# Janus.net
KiCad netlist of a schematic drawn in EAGLE
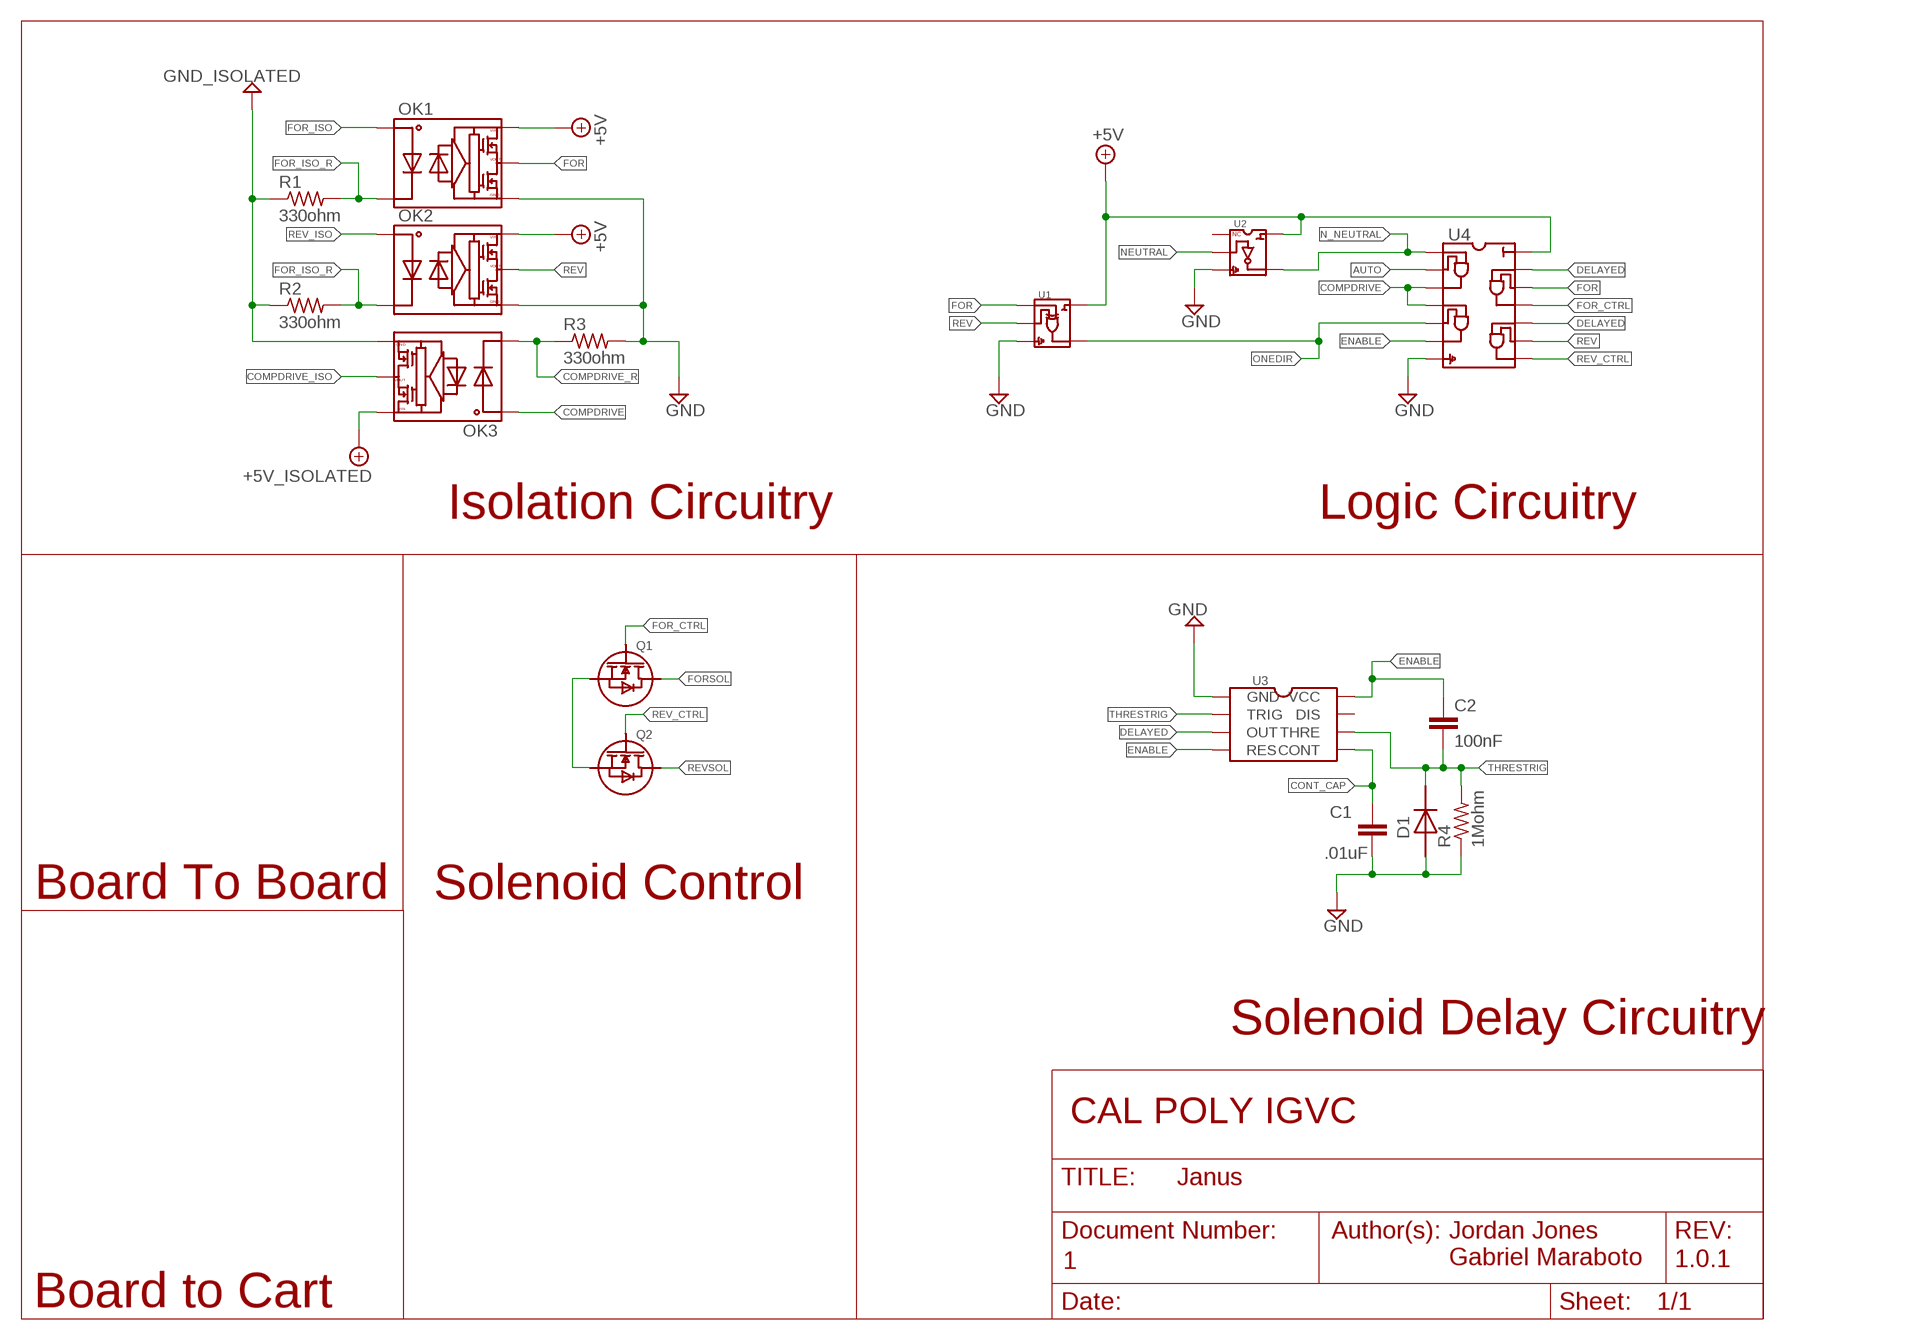
[diagram p0: schematic, sheet 1]

(export (version "E")
  (design (tool "Eeschema 10.0.6"))
  (components
    (comp (ref "C1")
      (value ".01uF")
      (footprint "eagle-import:C0603")
      (libsource (lib "eagle-import") (part "C-EUC0603"))
    )
    (comp (ref "C2")
      (value "100nF")
      (footprint "eagle-import:C0603")
      (libsource (lib "eagle-import") (part "C-EUC0603"))
    )
    (comp (ref "D1")
      (value "1N4148X-TP")
      (footprint "eagle-import:SOD523_SC79")
      (libsource (lib "eagle-import") (part "1N4148X-TP"))
    )
    (comp (ref "OK1")
      (value "TLP152")
      (footprint "eagle-import:6-SOIC-5")
      (libsource (lib "eagle-import") (part "TLP152"))
    )
    (comp (ref "OK2")
      (value "TLP152")
      (footprint "eagle-import:6-SOIC-5")
      (libsource (lib "eagle-import") (part "TLP152"))
    )
    (comp (ref "OK3")
      (value "TLP152")
      (footprint "eagle-import:6-SOIC-5")
      (libsource (lib "eagle-import") (part "TLP152"))
    )
    (comp (ref "Q1")
      (value "DMN6140L-7")
      (footprint "eagle-import:SOT23")
      (libsource (lib "eagle-import") (part "DMN6140L-7"))
    )
    (comp (ref "Q2")
      (value "DMN6140L-7")
      (footprint "eagle-import:SOT23")
      (libsource (lib "eagle-import") (part "DMN6140L-7"))
    )
    (comp (ref "R1")
      (value "330ohm")
      (footprint "eagle-import:R0603")
      (libsource (lib "eagle-import") (part "R-US_R0603"))
    )
    (comp (ref "R2")
      (value "330ohm")
      (footprint "eagle-import:R0603")
      (libsource (lib "eagle-import") (part "R-US_R0603"))
    )
    (comp (ref "R3")
      (value "330ohm")
      (footprint "eagle-import:R0603")
      (libsource (lib "eagle-import") (part "R-US_R0603"))
    )
    (comp (ref "R4")
      (value "1Mohm")
      (footprint "eagle-import:R0603")
      (libsource (lib "eagle-import") (part "R-US_R0603"))
    )
    (comp (ref "U1")
      (value "74LVC1G86W5-7")
      (footprint "eagle-import:SOT-25")
      (libsource (lib "eagle-import") (part "74LVC1G86W5-7"))
    )
    (comp (ref "U2")
      (value "74HCT1G14GW,125")
      (footprint "eagle-import:SOT-353")
      (libsource (lib "eagle-import") (part "74HCT1G14GW,125"))
    )
    (comp (ref "U3")
      (value "NE555S-13DICT-ND")
      (footprint "eagle-import:SO-8")
      (libsource (lib "eagle-import") (part "NE555S-13DICT-ND"))
    )
    (comp (ref "U4")
      (value "SN74LV08APWR")
      (footprint "eagle-import:TSSOP-14")
      (libsource (lib "eagle-import") (part "SN74LV08APWR"))
    )
  )
  (nets
    (net (code "1") (name "+5V") (class "Default")
      (node (ref "OK1") (pin "P$6") (pinfunction "P$6_P$6") (pintype "bidirectional"))
      (node (ref "OK2") (pin "P$6") (pinfunction "P$6_P$6") (pintype "bidirectional"))
      (node (ref "OK3") (pin "P$6") (pinfunction "P$6_P$6") (pintype "bidirectional"))
      (node (ref "U1") (pin "P$5") (pinfunction "P$5_P$5") (pintype "bidirectional"))
      (node (ref "U2") (pin "P$5") (pinfunction "P$5_P$5") (pintype "bidirectional"))
      (node (ref "U4") (pin "P$14") (pinfunction "P$14_P$14") (pintype "bidirectional"))
    )
    (net (code "2") (name "AUTO") (class "Default")
      (node (ref "U4") (pin "P$2") (pinfunction "P$2_P$2") (pintype "bidirectional"))
    )
    (net (code "3") (name "COMPDRIVE") (class "Default")
      (node (ref "OK3") (pin "P$1") (pinfunction "P$1_P$1") (pintype "bidirectional"))
      (node (ref "U4") (pin "P$3") (pinfunction "P$3_P$3") (pintype "bidirectional"))
      (node (ref "U4") (pin "P$4") (pinfunction "P$4_P$4") (pintype "bidirectional"))
    )
    (net (code "4") (name "COMPDRIVE_ISO") (class "Default")
      (node (ref "OK3") (pin "P$5") (pinfunction "P$5_P$5") (pintype "bidirectional"))
    )
    (net (code "5") (name "COMPDRIVE_R") (class "Default")
      (node (ref "OK3") (pin "P$3") (pinfunction "P$2_P$3") (pintype "bidirectional"))
      (node (ref "R3") (pin "1") (pinfunction "1_1") (pintype "passive"))
    )
    (net (code "6") (name "CONT_CAP") (class "Default")
      (node (ref "C1") (pin "1") (pinfunction "1_1") (pintype "passive"))
      (node (ref "U3") (pin "P$5") (pinfunction "CONT_P$5") (pintype "bidirectional"))
    )
    (net (code "7") (name "DELAYED") (class "Default")
      (node (ref "U3") (pin "P$3") (pinfunction "OUT_P$3") (pintype "bidirectional"))
      (node (ref "U4") (pin "P$10") (pinfunction "P$10_P$10") (pintype "bidirectional"))
      (node (ref "U4") (pin "P$13") (pinfunction "P$13_P$13") (pintype "bidirectional"))
    )
    (net (code "8") (name "ENABLE") (class "Default")
      (node (ref "C2") (pin "1") (pinfunction "1_1") (pintype "passive"))
      (node (ref "U3") (pin "P$4") (pinfunction "RES_P$4") (pintype "bidirectional"))
      (node (ref "U3") (pin "P$8") (pinfunction "VCC_P$8") (pintype "bidirectional"))
      (node (ref "U4") (pin "P$6") (pinfunction "P$6_P$6") (pintype "bidirectional"))
    )
    (net (code "9") (name "FOR") (class "Default")
      (node (ref "OK1") (pin "P$5") (pinfunction "P$5_P$5") (pintype "bidirectional"))
      (node (ref "U1") (pin "P$1") (pinfunction "P$1_P$1") (pintype "bidirectional"))
      (node (ref "U4") (pin "P$12") (pinfunction "P$12_P$12") (pintype "bidirectional"))
    )
    (net (code "10") (name "FORSOL") (class "Default")
      (node (ref "Q1") (pin "P$3") (pinfunction "D_P$3") (pintype "bidirectional"))
    )
    (net (code "11") (name "FOR_CTRL") (class "Default")
      (node (ref "Q1") (pin "P$1") (pinfunction "G_P$1") (pintype "bidirectional"))
      (node (ref "U4") (pin "P$11") (pinfunction "P$11_P$11") (pintype "bidirectional"))
    )
    (net (code "12") (name "FOR_ISO") (class "Default")
      (node (ref "OK1") (pin "P$1") (pinfunction "P$1_P$1") (pintype "bidirectional"))
    )
    (net (code "13") (name "FOR_ISO_R") (class "Default")
      (node (ref "OK1") (pin "P$3") (pinfunction "P$2_P$3") (pintype "bidirectional"))
      (node (ref "OK2") (pin "P$3") (pinfunction "P$2_P$3") (pintype "bidirectional"))
      (node (ref "R1") (pin "2") (pinfunction "2_2") (pintype "passive"))
      (node (ref "R2") (pin "2") (pinfunction "2_2") (pintype "passive"))
    )
    (net (code "14") (name "GND") (class "Default")
      (node (ref "C1") (pin "2") (pinfunction "2_2") (pintype "passive"))
      (node (ref "D1") (pin "P$1") (pinfunction "P$1_P$1") (pintype "bidirectional"))
      (node (ref "OK1") (pin "P$4") (pinfunction "P$4_P$4") (pintype "bidirectional"))
      (node (ref "OK2") (pin "P$4") (pinfunction "P$4_P$4") (pintype "bidirectional"))
      (node (ref "OK3") (pin "P$4") (pinfunction "P$4_P$4") (pintype "bidirectional"))
      (node (ref "R1") (pin "1") (pinfunction "1_1") (pintype "passive"))
      (node (ref "R2") (pin "1") (pinfunction "1_1") (pintype "passive"))
      (node (ref "R3") (pin "2") (pinfunction "2_2") (pintype "passive"))
      (node (ref "R4") (pin "1") (pinfunction "1_1") (pintype "passive"))
      (node (ref "U1") (pin "P$3") (pinfunction "P$3_P$3") (pintype "bidirectional"))
      (node (ref "U2") (pin "P$3") (pinfunction "P$3_P$3") (pintype "bidirectional"))
      (node (ref "U3") (pin "P$1") (pinfunction "GND_P$1") (pintype "bidirectional"))
      (node (ref "U4") (pin "P$7") (pinfunction "P$7_P$7") (pintype "bidirectional"))
    )
    (net (code "15") (name "NEUTRAL") (class "Default")
      (node (ref "U2") (pin "P$2") (pinfunction "P$2_P$2") (pintype "bidirectional"))
    )
    (net (code "16") (name "N_NEUTRAL") (class "Default")
      (node (ref "U2") (pin "P$4") (pinfunction "P$4_P$4") (pintype "bidirectional"))
      (node (ref "U4") (pin "P$1") (pinfunction "P$1_P$1") (pintype "bidirectional"))
    )
    (net (code "17") (name "Net-(Q1-S)") (class "Default")
      (node (ref "Q1") (pin "P$2") (pinfunction "S_P$2") (pintype "bidirectional"))
      (node (ref "Q2") (pin "P$2") (pinfunction "S_P$2") (pintype "bidirectional"))
    )
    (net (code "18") (name "ONEDIR") (class "Default")
      (node (ref "U1") (pin "P$4") (pinfunction "P$4_P$4") (pintype "bidirectional"))
      (node (ref "U4") (pin "P$5") (pinfunction "P$5_P$5") (pintype "bidirectional"))
    )
    (net (code "19") (name "REV") (class "Default")
      (node (ref "OK2") (pin "P$5") (pinfunction "P$5_P$5") (pintype "bidirectional"))
      (node (ref "U1") (pin "P$2") (pinfunction "P$2_P$2") (pintype "bidirectional"))
      (node (ref "U4") (pin "P$9") (pinfunction "P$9_P$9") (pintype "bidirectional"))
    )
    (net (code "20") (name "REVSOL") (class "Default")
      (node (ref "Q2") (pin "P$3") (pinfunction "D_P$3") (pintype "bidirectional"))
    )
    (net (code "21") (name "REV_CTRL") (class "Default")
      (node (ref "Q2") (pin "P$1") (pinfunction "G_P$1") (pintype "bidirectional"))
      (node (ref "U4") (pin "P$8") (pinfunction "P$8_P$8") (pintype "bidirectional"))
    )
    (net (code "22") (name "REV_ISO") (class "Default")
      (node (ref "OK2") (pin "P$1") (pinfunction "P$1_P$1") (pintype "bidirectional"))
    )
    (net (code "23") (name "THRESTRIG") (class "Default")
      (node (ref "C2") (pin "2") (pinfunction "2_2") (pintype "passive"))
      (node (ref "D1") (pin "P$2") (pinfunction "P$2_P$2") (pintype "bidirectional"))
      (node (ref "R4") (pin "2") (pinfunction "2_2") (pintype "passive"))
      (node (ref "U3") (pin "P$2") (pinfunction "TRIG_P$2") (pintype "bidirectional"))
      (node (ref "U3") (pin "P$6") (pinfunction "THRE_P$6") (pintype "bidirectional"))
    )
    (net (code "24") (name "unconnected-(U2-PadP$1)") (class "Default")
      (node (ref "U2") (pin "P$1") (pinfunction "P$1_P$1") (pintype "bidirectional"))
    )
    (net (code "25") (name "unconnected-(U3-DIS-PadP$7)") (class "Default")
      (node (ref "U3") (pin "P$7") (pinfunction "DIS_P$7") (pintype "bidirectional"))
    )
  )
)
